# marquee-power-PCB.net
KiCad netlist of a schematic drawn in EAGLE
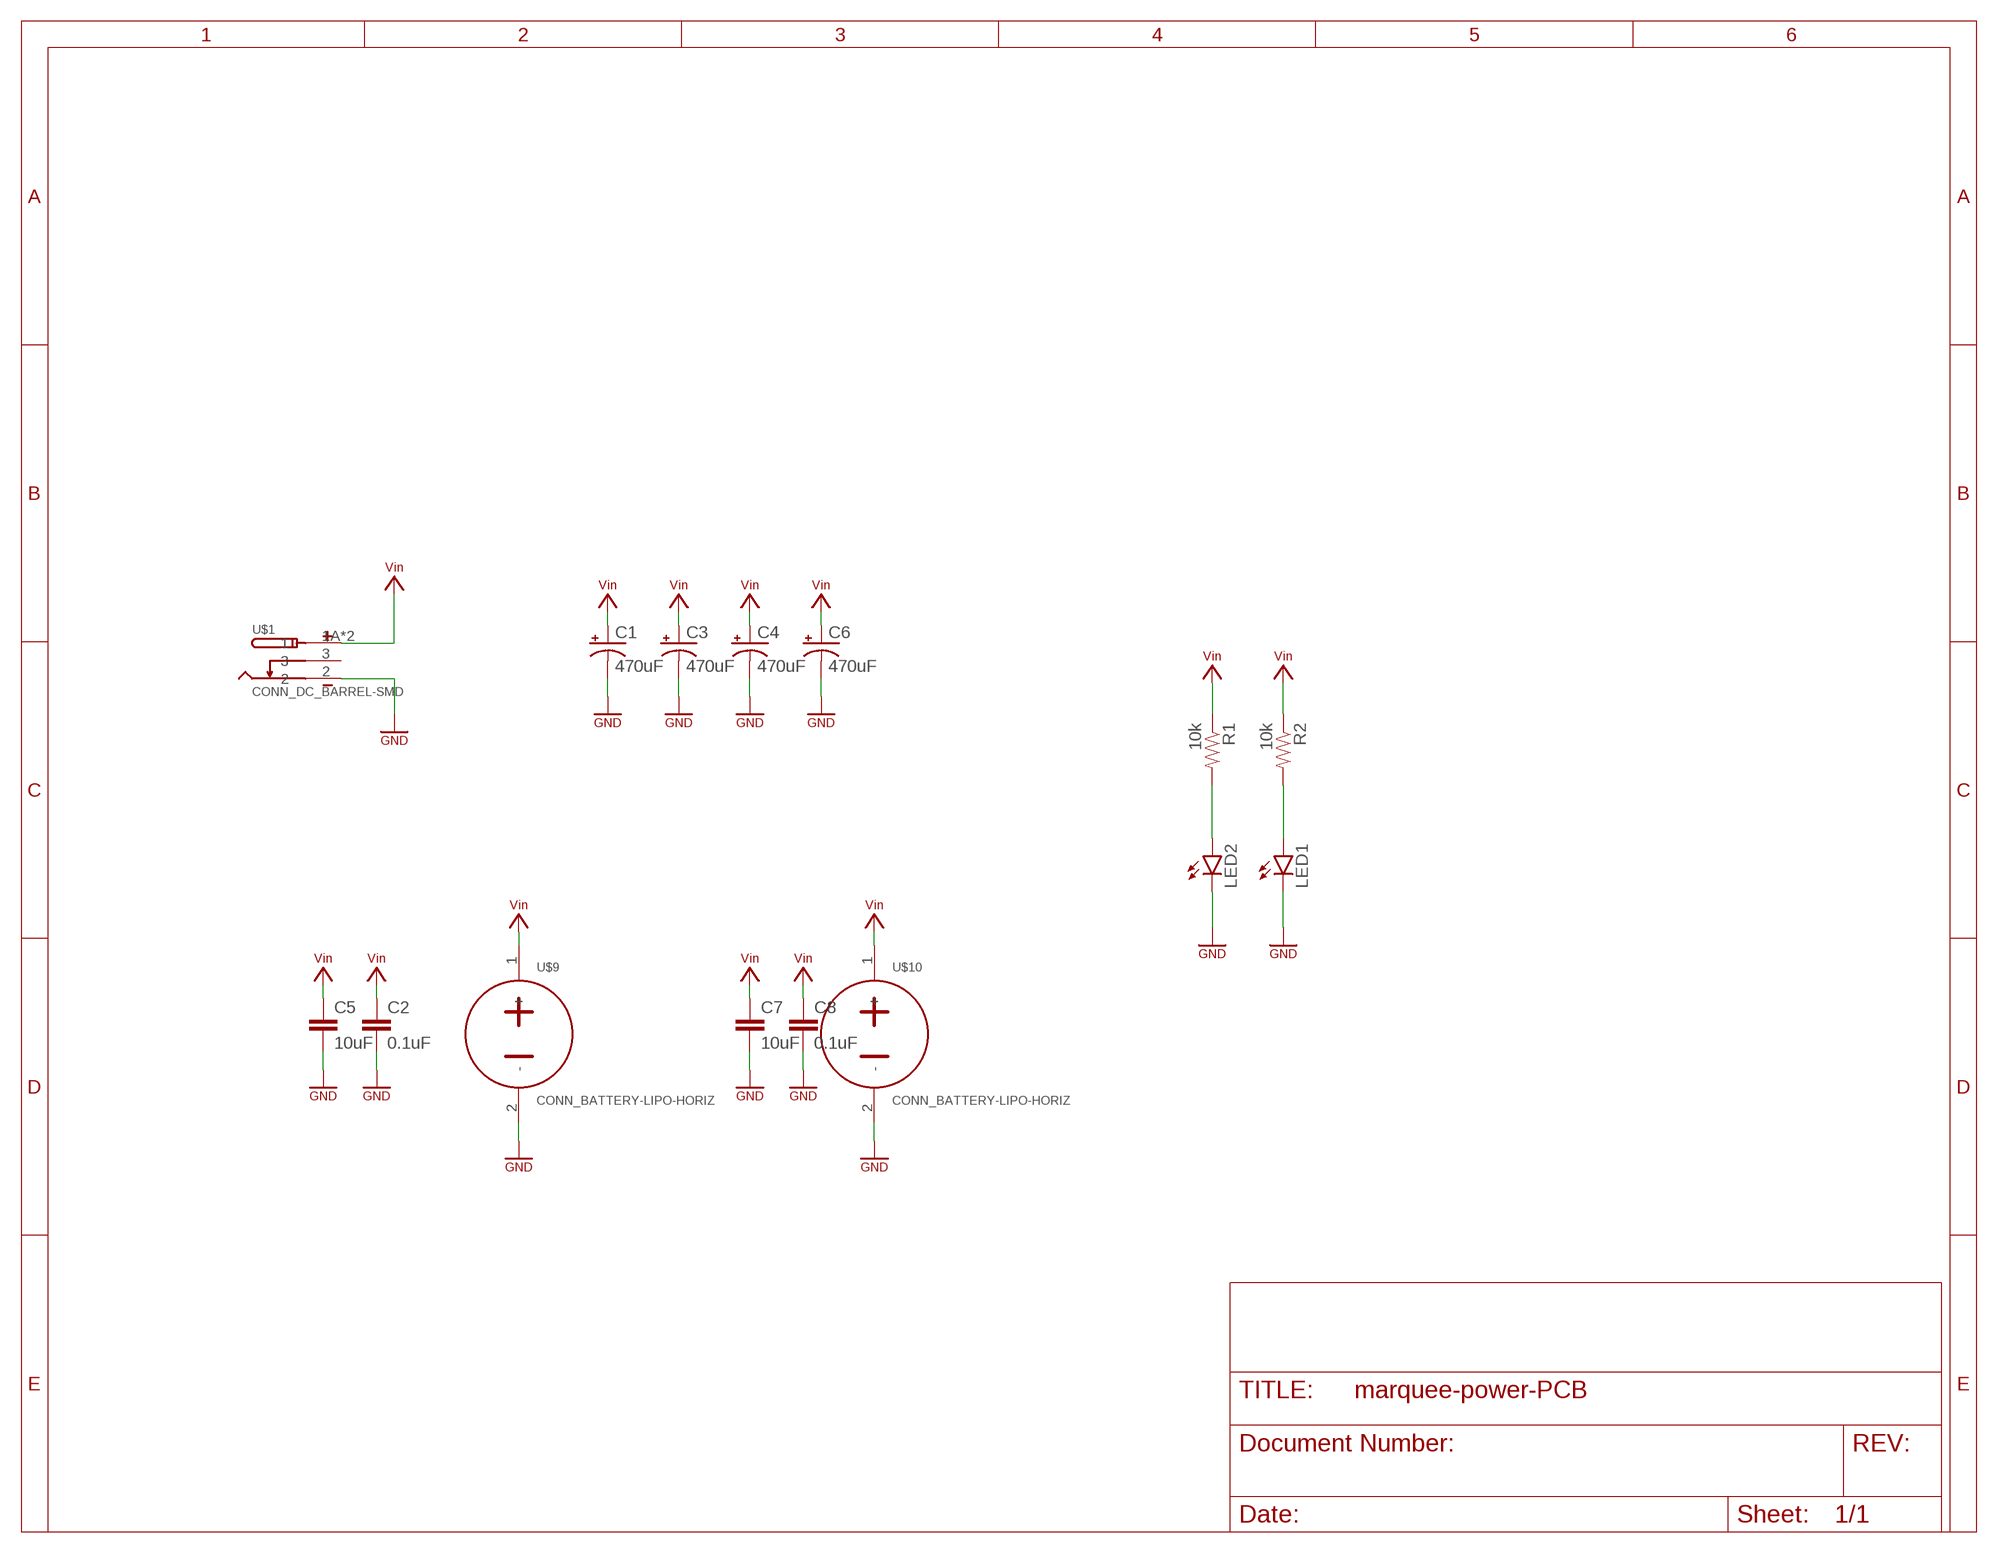
[diagram p0: schematic, sheet 1]

(export (version "E")
  (design (tool "Eeschema 10.0.6"))
  (components
    (comp (ref "C1")
      (value "470uF")
      (footprint "eagle-import:CAP_RADIAL_CAN_10MM")
      (libsource (lib "eagle-import") (part "COMPONENT_CAP_POL-10MM"))
    )
    (comp (ref "C2")
      (value "0.1uF")
      (footprint "eagle-import:0805")
      (libsource (lib "eagle-import") (part "COMPONENT_CAP-0805"))
    )
    (comp (ref "C3")
      (value "470uF")
      (footprint "eagle-import:CAP_RADIAL_CAN_10MM")
      (libsource (lib "eagle-import") (part "COMPONENT_CAP_POL-10MM"))
    )
    (comp (ref "C4")
      (value "470uF")
      (footprint "eagle-import:CAP_RADIAL_CAN_10MM")
      (libsource (lib "eagle-import") (part "COMPONENT_CAP_POL-10MM"))
    )
    (comp (ref "C5")
      (value "10uF")
      (footprint "eagle-import:0805")
      (libsource (lib "eagle-import") (part "COMPONENT_CAP-0805"))
    )
    (comp (ref "C6")
      (value "470uF")
      (footprint "eagle-import:CAP_RADIAL_CAN_10MM")
      (libsource (lib "eagle-import") (part "COMPONENT_CAP_POL-10MM"))
    )
    (comp (ref "C7")
      (value "10uF")
      (footprint "eagle-import:0805")
      (libsource (lib "eagle-import") (part "COMPONENT_CAP-0805"))
    )
    (comp (ref "C8")
      (value "0.1uF")
      (footprint "eagle-import:0805")
      (libsource (lib "eagle-import") (part "COMPONENT_CAP-0805"))
    )
    (comp (ref "LED1")
      (value "LED-0805")
      (footprint "eagle-import:CHIP-LED0805")
      (libsource (lib "eagle-import") (part "LED-0805"))
    )
    (comp (ref "LED2")
      (value "LED-0805")
      (footprint "eagle-import:CHIP-LED0805")
      (libsource (lib "eagle-import") (part "LED-0805"))
    )
    (comp (ref "R1")
      (value "10k")
      (footprint "eagle-import:0805")
      (libsource (lib "eagle-import") (part "COMPONENT_RESISTOR-0805"))
    )
    (comp (ref "R2")
      (value "10k")
      (footprint "eagle-import:0805")
      (libsource (lib "eagle-import") (part "COMPONENT_RESISTOR-0805"))
    )
    (comp (ref "U$1")
      (value "CONN_DC_BARREL-SMD")
      (footprint "eagle-import:694106106102")
      (libsource (lib "eagle-import") (part "CONN_DC_BARREL-SMD"))
    )
    (comp (ref "U$9")
      (value "CONN_BATTERY-LIPO-HORIZ")
      (footprint "eagle-import:JST-PH-2-SMT-RA")
      (libsource (lib "eagle-import") (part "CONN_BATTERY-LIPO-HORIZ"))
    )
    (comp (ref "U$10")
      (value "CONN_BATTERY-LIPO-HORIZ")
      (footprint "eagle-import:JST-PH-2-SMT-RA")
      (libsource (lib "eagle-import") (part "CONN_BATTERY-LIPO-HORIZ"))
    )
  )
  (nets
    (net (code "1") (name "Net-(LED1-PadA)") (class "Default")
      (node (ref "LED1") (pin "A") (pinfunction "A_A") (pintype "passive"))
      (node (ref "R2") (pin "2") (pinfunction "2_2") (pintype "passive"))
    )
    (net (code "2") (name "Net-(LED2-PadA)") (class "Default")
      (node (ref "LED2") (pin "A") (pinfunction "A_A") (pintype "passive"))
      (node (ref "R1") (pin "2") (pinfunction "2_2") (pintype "passive"))
    )
    (net (code "3") (name "SYMBOL_GND") (class "Default")
      (node (ref "C1") (pin "-") (pinfunction "-_-") (pintype "passive"))
      (node (ref "C2") (pin "2") (pinfunction "2_2") (pintype "passive"))
      (node (ref "C3") (pin "-") (pinfunction "-_-") (pintype "passive"))
      (node (ref "C4") (pin "-") (pinfunction "-_-") (pintype "passive"))
      (node (ref "C5") (pin "2") (pinfunction "2_2") (pintype "passive"))
      (node (ref "C6") (pin "-") (pinfunction "-_-") (pintype "passive"))
      (node (ref "C7") (pin "2") (pinfunction "2_2") (pintype "passive"))
      (node (ref "C8") (pin "2") (pinfunction "2_2") (pintype "passive"))
      (node (ref "LED1") (pin "C") (pinfunction "C_C") (pintype "passive"))
      (node (ref "LED2") (pin "C") (pinfunction "C_C") (pintype "passive"))
      (node (ref "U$1") (pin "2") (pinfunction "2_2") (pintype "bidirectional"))
      (node (ref "U$10") (pin "2") (pinfunction "-_2") (pintype "bidirectional"))
      (node (ref "U$9") (pin "2") (pinfunction "-_2") (pintype "bidirectional"))
    )
    (net (code "4") (name "SYMBOL_VIN") (class "Default")
      (node (ref "C1") (pin "+") (pinfunction "+_+") (pintype "passive"))
      (node (ref "C2") (pin "1") (pinfunction "1_1") (pintype "passive"))
      (node (ref "C3") (pin "+") (pinfunction "+_+") (pintype "passive"))
      (node (ref "C4") (pin "+") (pinfunction "+_+") (pintype "passive"))
      (node (ref "C5") (pin "1") (pinfunction "1_1") (pintype "passive"))
      (node (ref "C6") (pin "+") (pinfunction "+_+") (pintype "passive"))
      (node (ref "C7") (pin "1") (pinfunction "1_1") (pintype "passive"))
      (node (ref "C8") (pin "1") (pinfunction "1_1") (pintype "passive"))
      (node (ref "R1") (pin "1") (pinfunction "1_1") (pintype "passive"))
      (node (ref "R2") (pin "1") (pinfunction "1_1") (pintype "passive"))
      (node (ref "U$1") (pin "1A") (pinfunction "1_1A") (pintype "bidirectional"))
      (node (ref "U$1") (pin "1B") (pinfunction "1_1B") (pintype "bidirectional"))
      (node (ref "U$10") (pin "1") (pinfunction "+_1") (pintype "bidirectional"))
      (node (ref "U$9") (pin "1") (pinfunction "+_1") (pintype "bidirectional"))
    )
    (net (code "5") (name "unconnected-(U$1-Pad3)") (class "Default")
      (node (ref "U$1") (pin "3") (pinfunction "3_3") (pintype "bidirectional"))
    )
  )
)
